# SCH_RemdesKVM_2025-04-20.net
KiCad netlist of a schematic drawn in EasyEDA
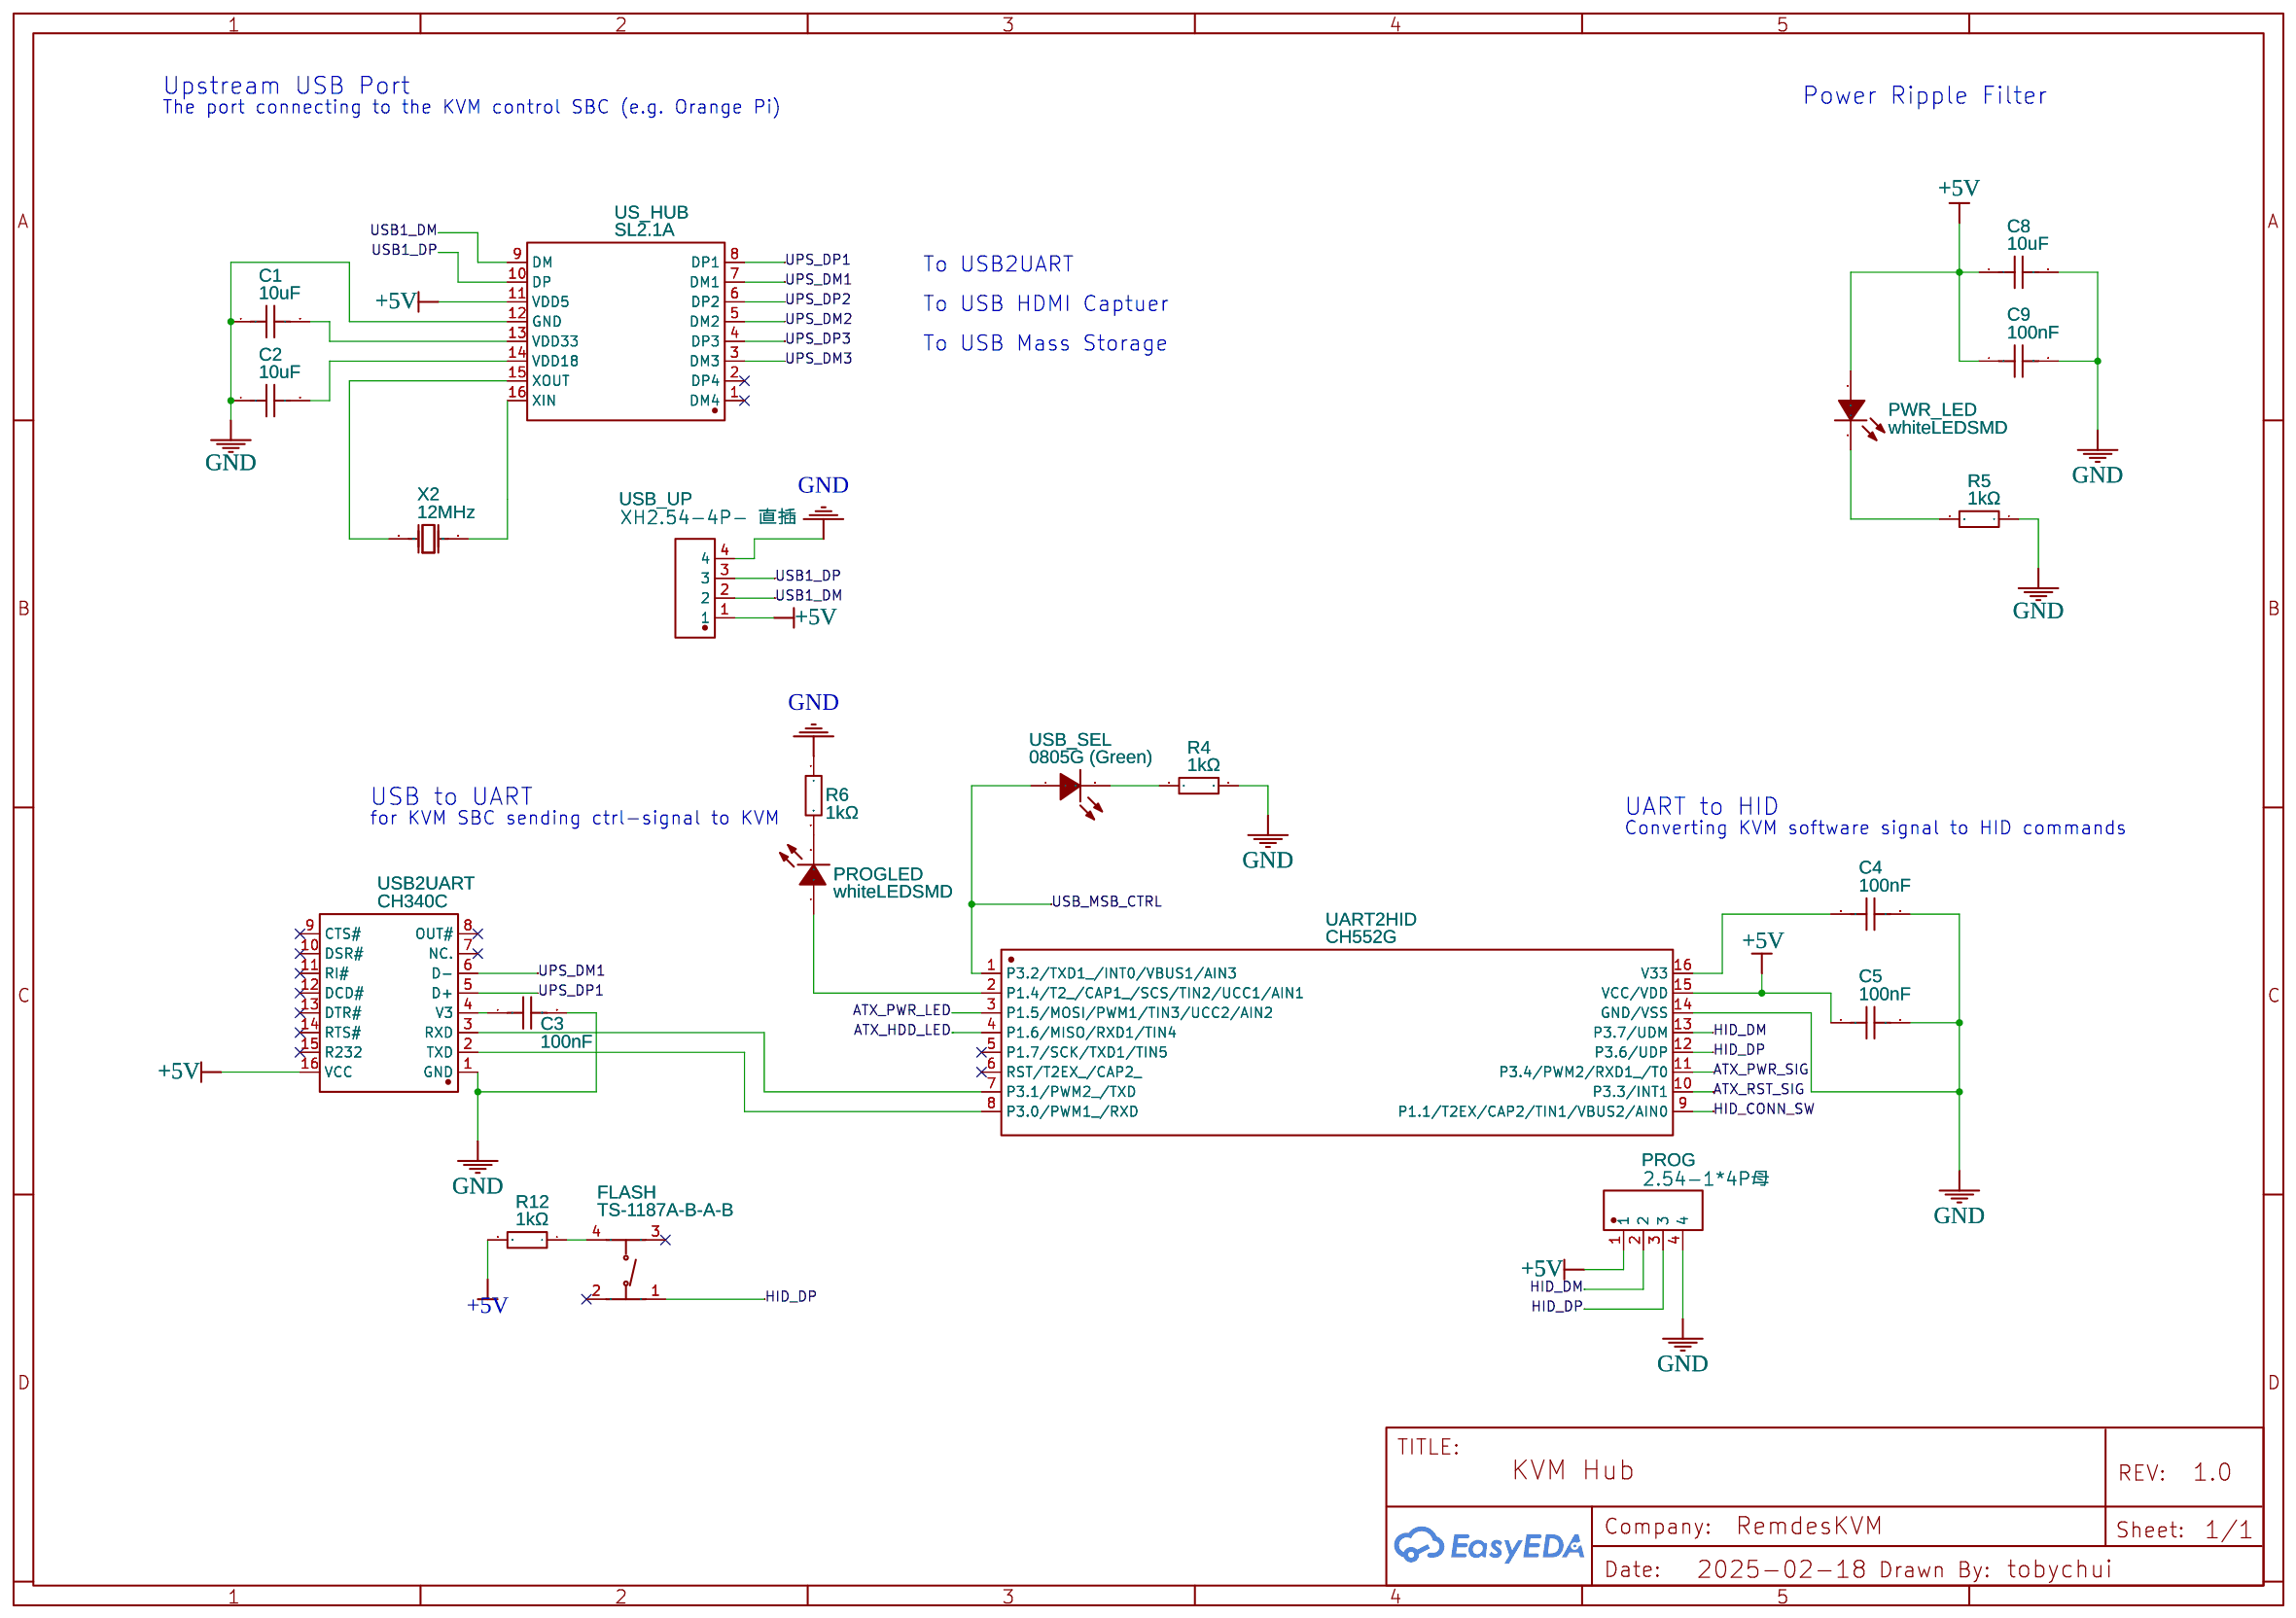
[diagram p0: KVM]
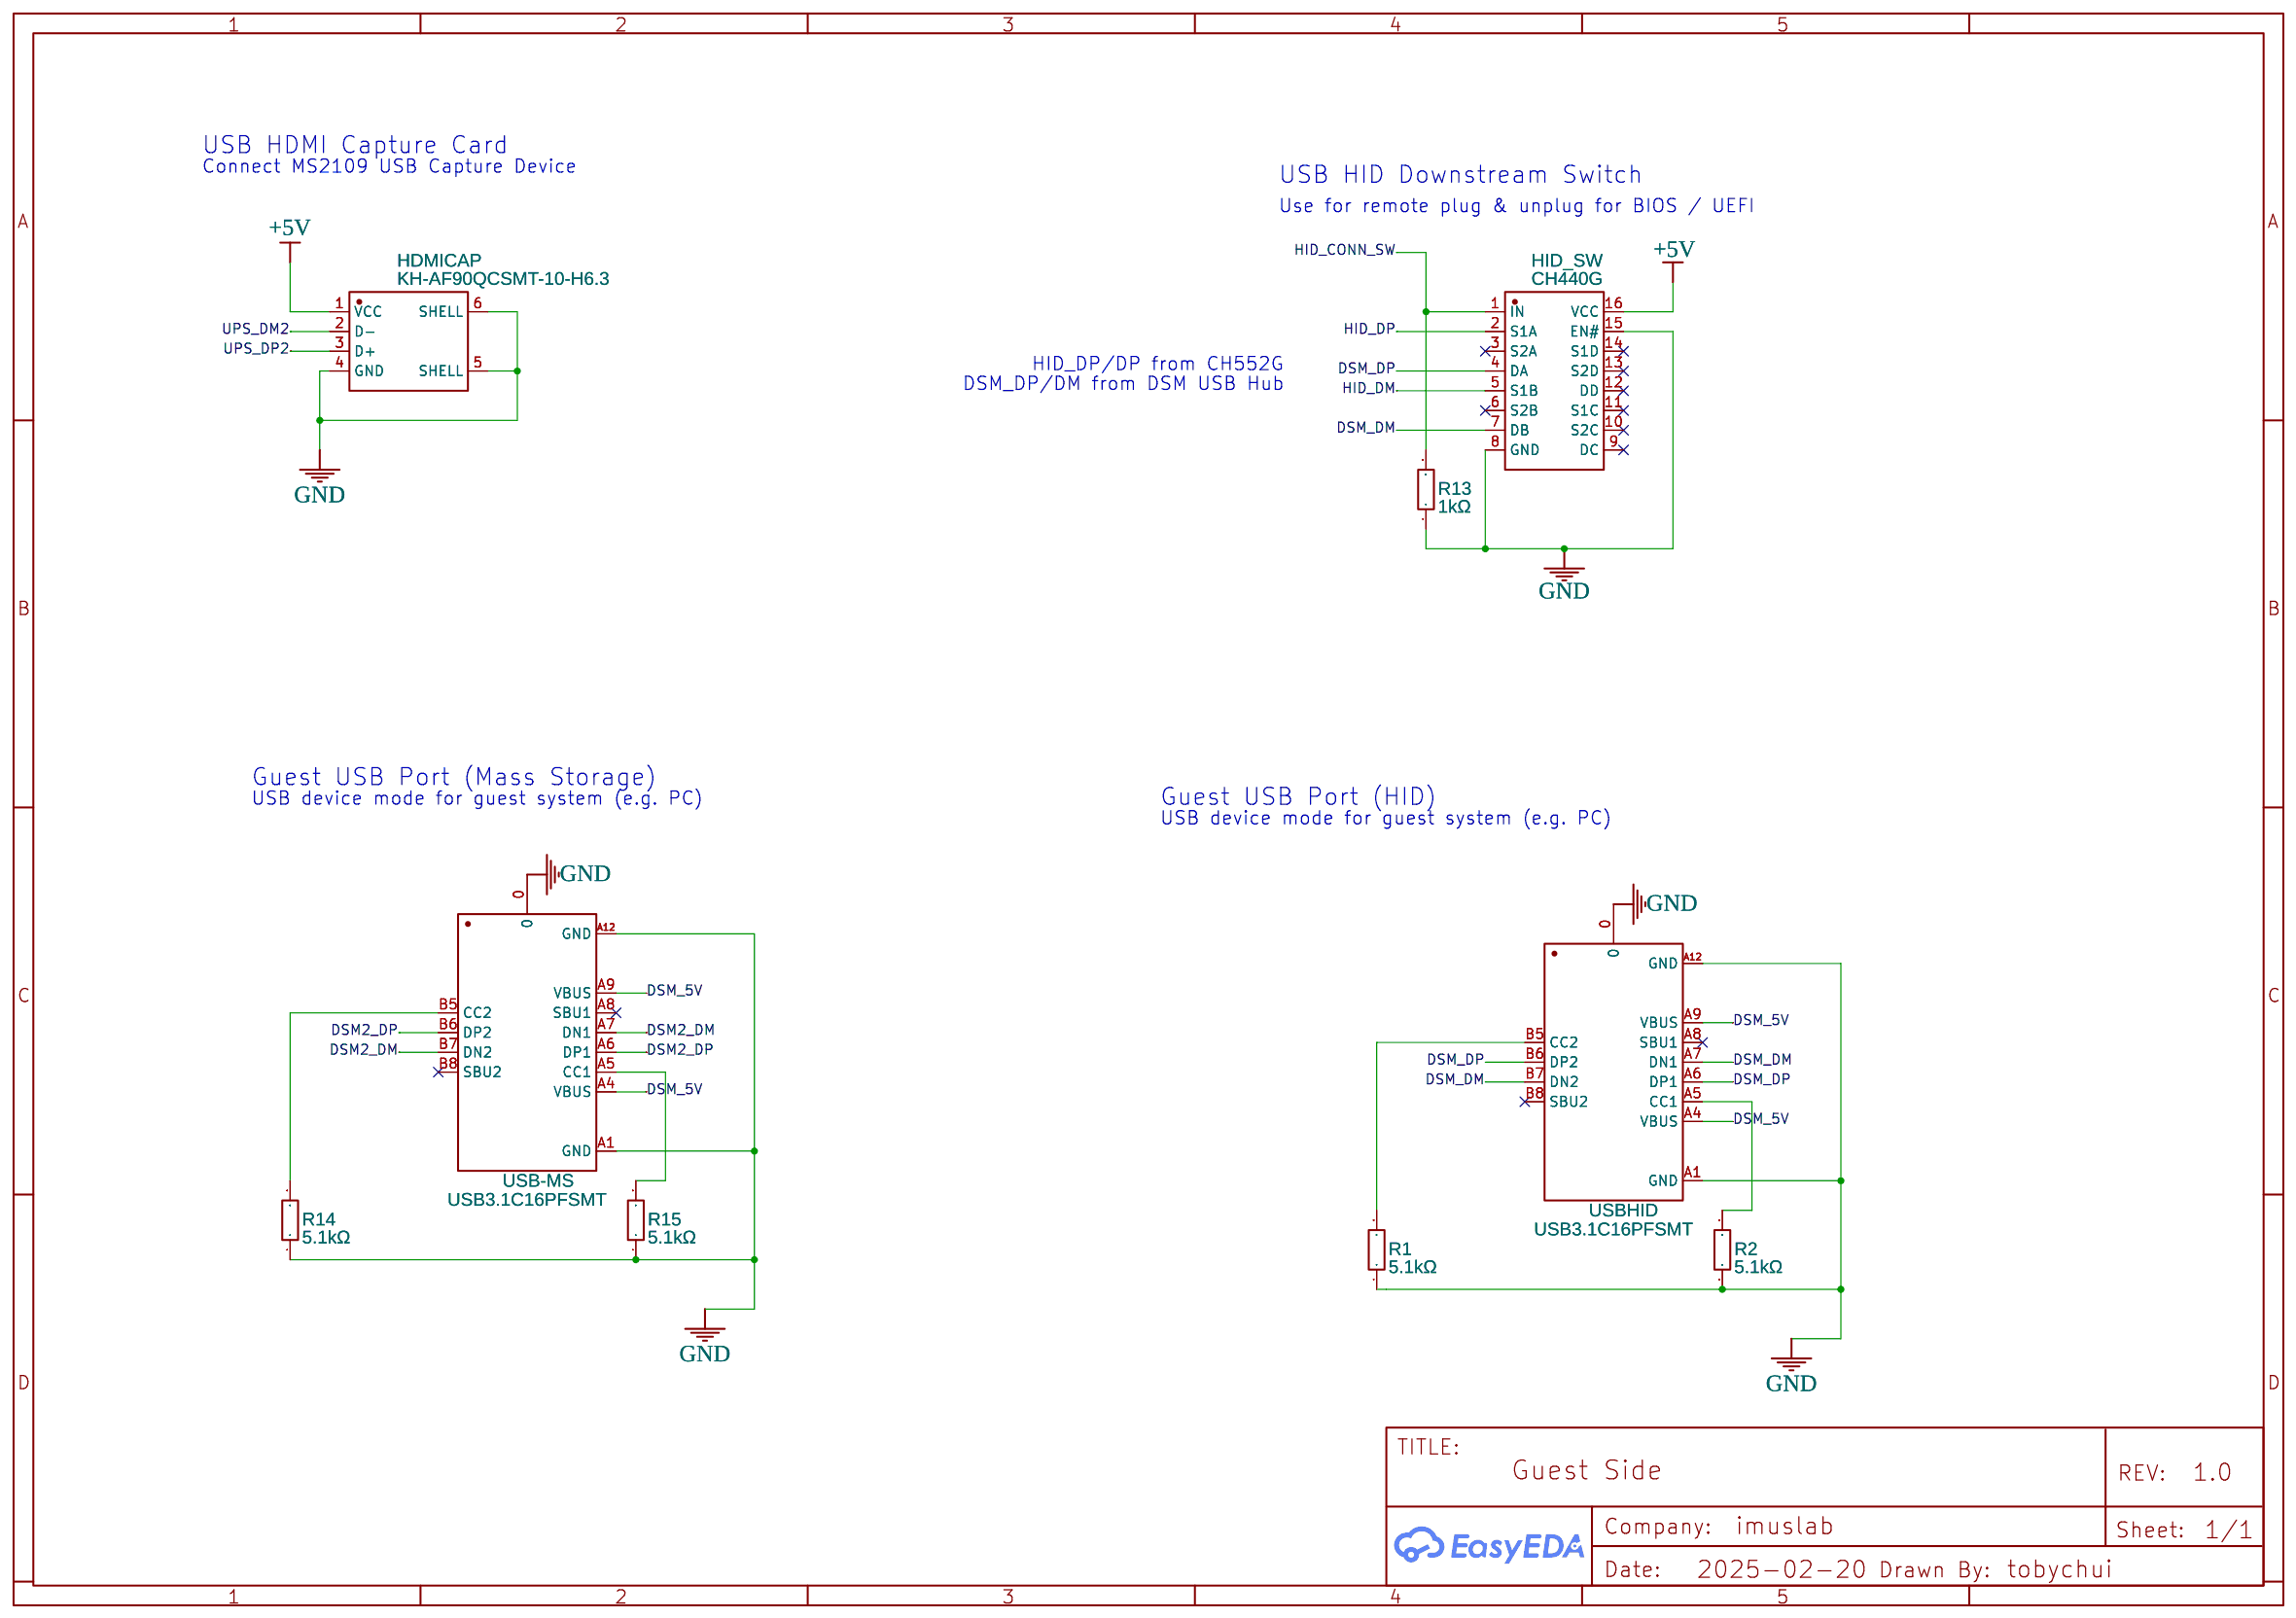
[diagram p1: Guest]
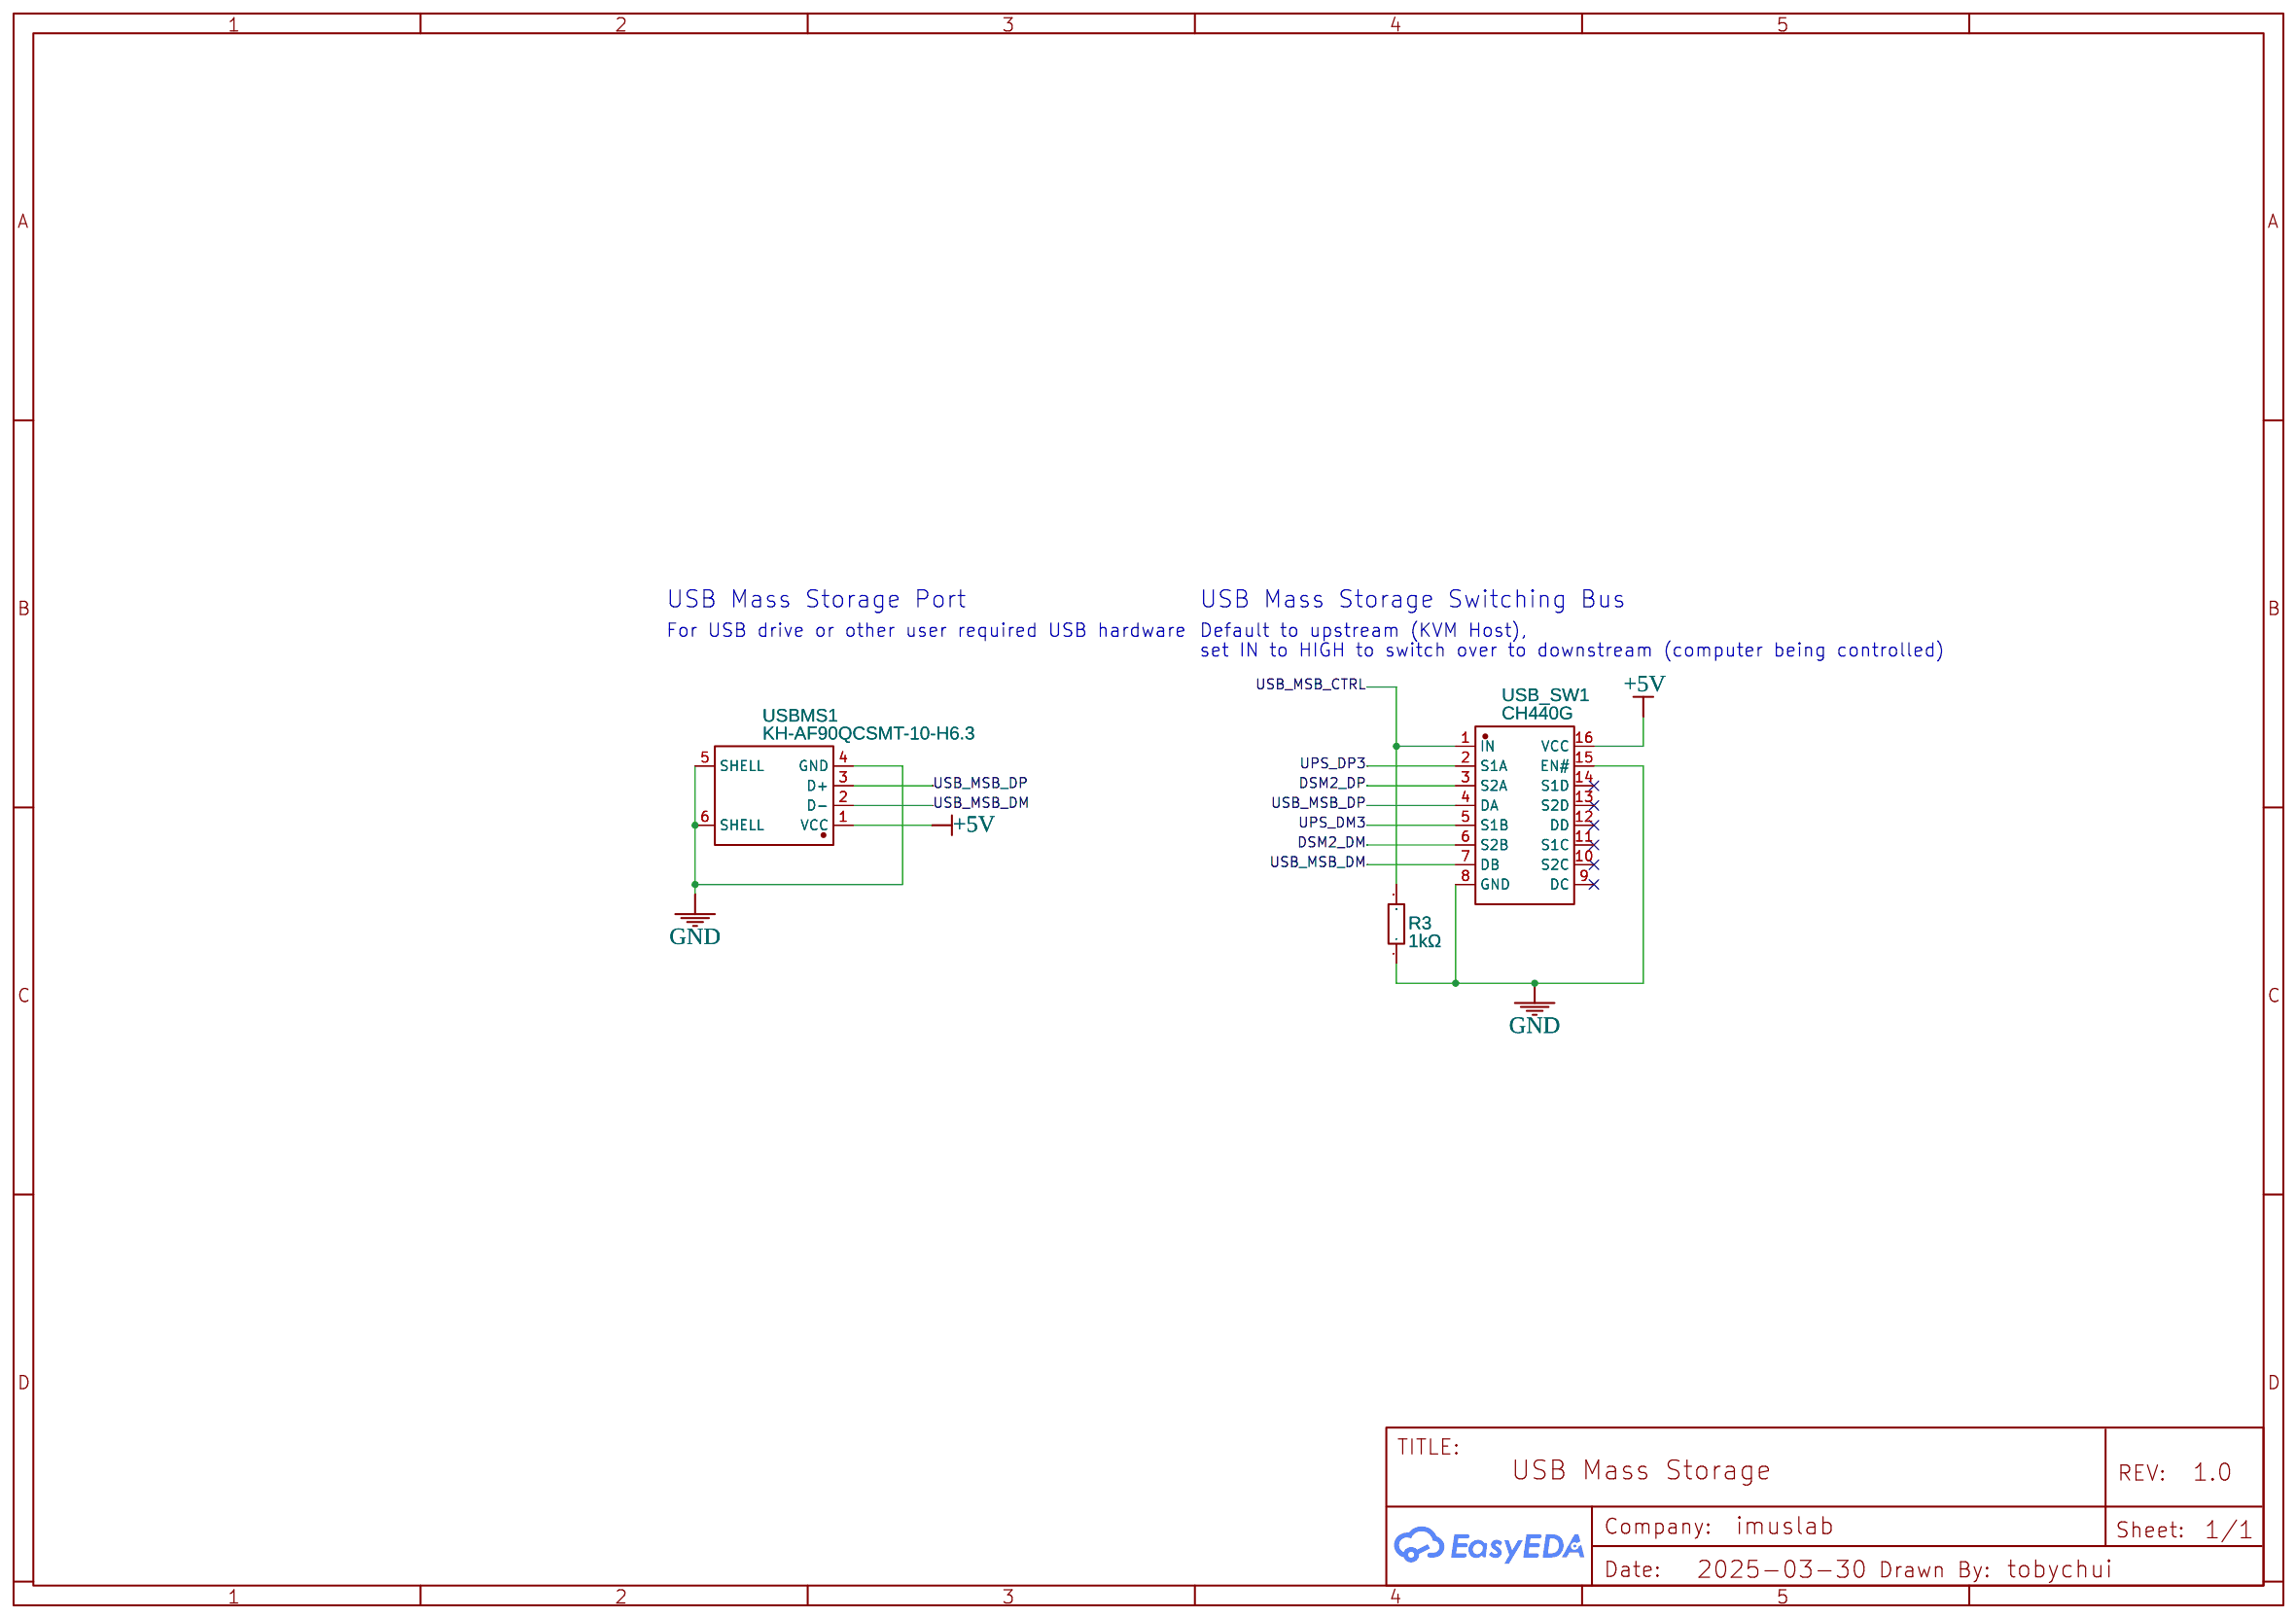
[diagram p2: USB Mass Storage]
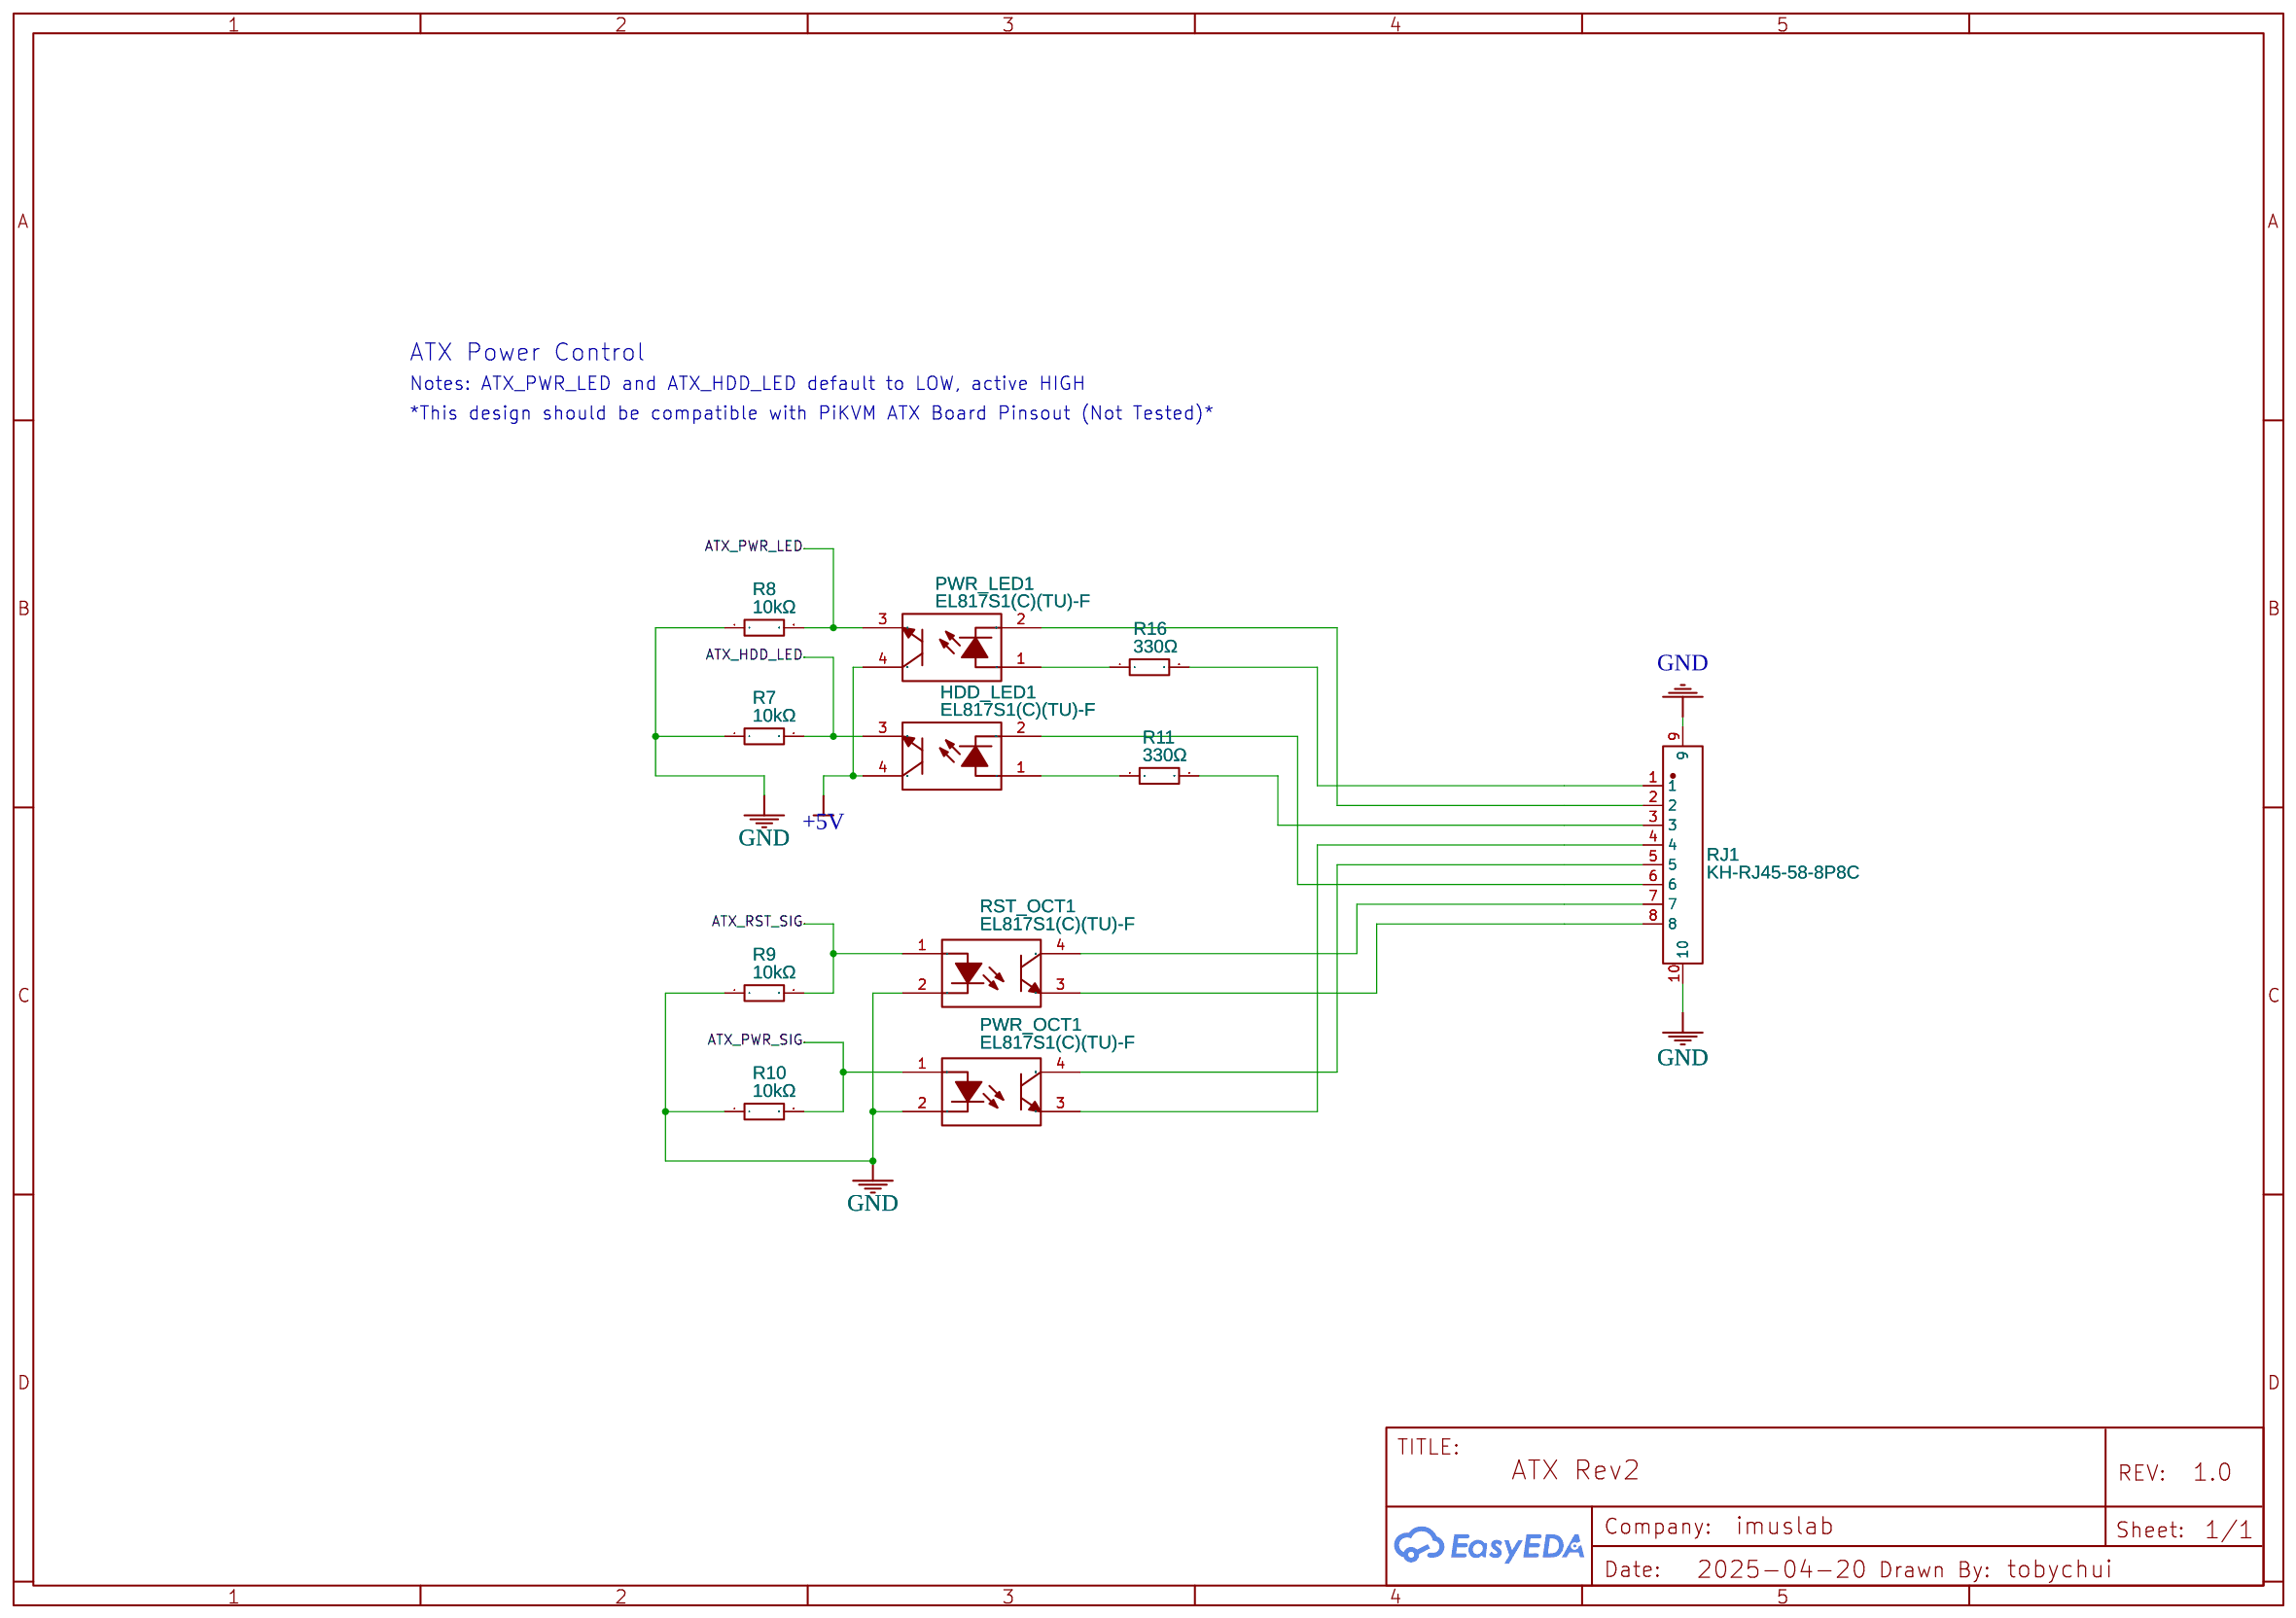
[diagram p3: ATX]

(export (version "E")
  (design (tool "Eeschema 10.0.6"))
  (components
    (comp (ref "C1")
      (value "10uF")
      (fields
        (field (name "Manufacturer Part") "CL21A106KAYNNNE")
        (field (name "Manufacturer") "SAMSUNG(三星)")
      )
      (libsource (lib "") (part "CL21A106KAYNNNE"))
    )
    (comp (ref "C2")
      (value "10uF")
      (fields
        (field (name "Manufacturer Part") "CL21A106KAYNNNE")
        (field (name "Manufacturer") "SAMSUNG(三星)")
      )
      (libsource (lib "") (part "CL21A106KAYNNNE"))
    )
    (comp (ref "C3")
      (value "100nF")
      (fields
        (field (name "Manufacturer Part") "CC0805KRX7R9BB104")
        (field (name "Manufacturer") "YAGEO(国巨)")
      )
      (libsource (lib "") (part "CC0805KRX7R9BB104"))
    )
    (comp (ref "C4")
      (value "100nF")
      (fields
        (field (name "Manufacturer Part") "CC0805KRX7R9BB104")
        (field (name "Manufacturer") "YAGEO(国巨)")
      )
      (libsource (lib "") (part "CC0805KRX7R9BB104"))
    )
    (comp (ref "C5")
      (value "100nF")
      (fields
        (field (name "Manufacturer Part") "CC0805KRX7R9BB104")
        (field (name "Manufacturer") "YAGEO(国巨)")
      )
      (libsource (lib "") (part "CC0805KRX7R9BB104"))
    )
    (comp (ref "C8")
      (value "10uF")
      (fields
        (field (name "Manufacturer Part") "CL21A106KAYNNNE")
        (field (name "Manufacturer") "SAMSUNG(三星)")
      )
      (libsource (lib "") (part "CL21A106KAYNNNE"))
    )
    (comp (ref "C9")
      (value "100nF")
      (fields
        (field (name "Manufacturer Part") "CC0805KRX7R9BB104")
        (field (name "Manufacturer") "YAGEO(国巨)")
      )
      (libsource (lib "") (part "CC0805KRX7R9BB104"))
    )
    (comp (ref "FLASH")
      (value "TS-1187A-B-A-B")
      (fields (field (name "Manufacturer") "XKB Connectivity(中国星坤)"))
      (libsource (lib "") (part "TS-1187A-B-A-B"))
    )
    (comp (ref "PROG")
      (value "2.54-1*4P母")
      (fields (field (name "Manufacturer") "BOOMELE(博穆精密)"))
      (libsource (lib "") (part "2.54-1*4P母"))
    )
    (comp (ref "PROGLED")
      (value "whiteLEDSMD")
      (fields (field (name "Manufacturer Part") "KT-0805W") (field (name "Manufacturer") "KENTO"))
      (libsource (lib "") (part "whiteLEDSMD_1"))
    )
    (comp (ref "PWR_LED")
      (value "whiteLEDSMD")
      (fields (field (name "Manufacturer Part") "KT-0805W") (field (name "Manufacturer") "KENTO"))
      (libsource (lib "") (part "whiteLEDSMD"))
    )
    (comp (ref "R4")
      (value "1kΩ")
      (fields
        (field (name "Manufacturer Part") "0805W8F1001T5E")
        (field (name "Manufacturer") "UNI-ROYAL(厚声)")
      )
      (libsource (lib "") (part "0805W8F1001T5E"))
    )
    (comp (ref "R5")
      (value "1kΩ")
      (fields
        (field (name "Manufacturer Part") "0805W8F1001T5E")
        (field (name "Manufacturer") "UNI-ROYAL(厚声)")
      )
      (libsource (lib "") (part "0805W8F1001T5E"))
    )
    (comp (ref "R6")
      (value "1kΩ")
      (fields
        (field (name "Manufacturer Part") "0805W8F1001T5E")
        (field (name "Manufacturer") "UNI-ROYAL(厚声)")
      )
      (libsource (lib "") (part "0805W8F1001T5E_1"))
    )
    (comp (ref "R12")
      (value "1kΩ")
      (fields
        (field (name "Manufacturer Part") "0805W8F1001T5E")
        (field (name "Manufacturer") "UNI-ROYAL(厚声)")
      )
      (libsource (lib "") (part "0805W8F1001T5E"))
    )
    (comp (ref "UART2HID")
      (value "CH552G")
      (fields (field (name "Manufacturer") "WCH(南京沁恒)"))
      (libsource (lib "") (part "CH552G"))
    )
    (comp (ref "USB2UART")
      (value "CH340C")
      (fields (field (name "Manufacturer") "WCH(南京沁恒)"))
      (libsource (lib "") (part "CH340C"))
    )
    (comp (ref "USB_SEL")
      (value "0805G (Green)")
      (fields (field (name "Manufacturer Part") "KT-0805G") (field (name "Manufacturer") "KENTO"))
      (libsource (lib "") (part "0805G (Green)"))
    )
    (comp (ref "USB_UP") (value "XH2.54-4P- 直插") (libsource (lib "") (part "XH2.54-4P- 直插")))
    (comp (ref "US_HUB")
      (value "SL2.1A")
      (fields (field (name "Manufacturer") "CoreChips(和芯润德)"))
      (libsource (lib "") (part "SL2.1A"))
    )
    (comp (ref "X2")
      (value "12MHz")
      (fields (field (name "Manufacturer Part") "X503212MSD2GI") (field (name "Manufacturer") "YXC(扬兴晶振)"))
      (libsource (lib "") (part "X503212MSD2GI"))
    )
    (comp (ref "HDMICAP")
      (value "KH-AF90QCSMT-10-H6.3")
      (fields (field (name "Manufacturer") "kinghelm(金航标)"))
      (libsource (lib "") (part "KH-AF90QCSMT-10-H6.3"))
    )
    (comp (ref "HID_SW")
      (value "CH440G")
      (fields (field (name "Manufacturer") "WCH(南京沁恒)"))
      (libsource (lib "") (part "CH440G"))
    )
    (comp (ref "R1")
      (value "5.1kΩ")
      (fields
        (field (name "Manufacturer Part") "0805W8F5101T5E")
        (field (name "Manufacturer") "UNI-ROYAL(厚声)")
      )
      (libsource (lib "") (part "0805W8F5101T5E"))
    )
    (comp (ref "R2")
      (value "5.1kΩ")
      (fields
        (field (name "Manufacturer Part") "0805W8F5101T5E")
        (field (name "Manufacturer") "UNI-ROYAL(厚声)")
      )
      (libsource (lib "") (part "0805W8F5101T5E"))
    )
    (comp (ref "R13")
      (value "1kΩ")
      (fields
        (field (name "Manufacturer Part") "0805W8F1001T5E")
        (field (name "Manufacturer") "UNI-ROYAL(厚声)")
      )
      (libsource (lib "") (part "0805W8F1001T5E"))
    )
    (comp (ref "R14")
      (value "5.1kΩ")
      (fields
        (field (name "Manufacturer Part") "0805W8F5101T5E")
        (field (name "Manufacturer") "UNI-ROYAL(厚声)")
      )
      (libsource (lib "") (part "0805W8F5101T5E"))
    )
    (comp (ref "R15")
      (value "5.1kΩ")
      (fields
        (field (name "Manufacturer Part") "0805W8F5101T5E")
        (field (name "Manufacturer") "UNI-ROYAL(厚声)")
      )
      (libsource (lib "") (part "0805W8F5101T5E"))
    )
    (comp (ref "USB-MS")
      (value "USB3.1C16PFSMT")
      (fields (field (name "Manufacturer Part") "918-418K2023S40001") (field (name "Manufacturer") "精拓金"))
      (libsource (lib "") (part "USB3.1C16PFSMT"))
    )
    (comp (ref "USBHID")
      (value "USB3.1C16PFSMT")
      (fields (field (name "Manufacturer Part") "918-418K2023S40001") (field (name "Manufacturer") "精拓金"))
      (libsource (lib "") (part "USB3.1C16PFSMT_1"))
    )
    (comp (ref "R3")
      (value "1kΩ")
      (fields
        (field (name "Manufacturer Part") "0805W8F1001T5E")
        (field (name "Manufacturer") "UNI-ROYAL(厚声)")
      )
      (libsource (lib "") (part "0805W8F1001T5E"))
    )
    (comp (ref "USBMS1")
      (value "KH-AF90QCSMT-10-H6.3")
      (fields (field (name "Manufacturer") "kinghelm(金航标)"))
      (libsource (lib "") (part "KH-AF90QCSMT-10-H6.3"))
    )
    (comp (ref "USB_SW1")
      (value "CH440G")
      (fields (field (name "Manufacturer") "WCH(南京沁恒)"))
      (libsource (lib "") (part "CH440G"))
    )
    (comp (ref "HDD_LED1")
      (value "EL817S1(C)(TU)-F")
      (fields (field (name "Manufacturer") "EVERLIGHT(亿光)"))
      (libsource (lib "") (part "EL817S1(C)(TU)-F_2"))
    )
    (comp (ref "PWR_LED1")
      (value "EL817S1(C)(TU)-F")
      (fields (field (name "Manufacturer") "EVERLIGHT(亿光)"))
      (libsource (lib "") (part "EL817S1(C)(TU)-F_3"))
    )
    (comp (ref "PWR_OCT1")
      (value "EL817S1(C)(TU)-F")
      (fields (field (name "Manufacturer") "EVERLIGHT(亿光)"))
      (libsource (lib "") (part "EL817S1(C)(TU)-F"))
    )
    (comp (ref "R7")
      (value "10kΩ")
      (fields
        (field (name "Manufacturer Part") "0805W8F1002T5E")
        (field (name "Manufacturer") "UNI-ROYAL(厚声)")
      )
      (libsource (lib "") (part "0805W8F1002T5E"))
    )
    (comp (ref "R8")
      (value "10kΩ")
      (fields
        (field (name "Manufacturer Part") "0805W8F1002T5E")
        (field (name "Manufacturer") "UNI-ROYAL(厚声)")
      )
      (libsource (lib "") (part "0805W8F1002T5E"))
    )
    (comp (ref "R9")
      (value "10kΩ")
      (fields
        (field (name "Manufacturer Part") "0805W8F1002T5E")
        (field (name "Manufacturer") "UNI-ROYAL(厚声)")
      )
      (libsource (lib "") (part "0805W8F1002T5E"))
    )
    (comp (ref "R10")
      (value "10kΩ")
      (fields
        (field (name "Manufacturer Part") "0805W8F1002T5E")
        (field (name "Manufacturer") "UNI-ROYAL(厚声)")
      )
      (libsource (lib "") (part "0805W8F1002T5E"))
    )
    (comp (ref "R11")
      (value "330Ω")
      (fields
        (field (name "Manufacturer Part") "0805W8F3300T5E")
        (field (name "Manufacturer") "UNI-ROYAL(厚声)")
      )
      (libsource (lib "") (part "0805W8F3300T5E"))
    )
    (comp (ref "R16")
      (value "330Ω")
      (fields
        (field (name "Manufacturer Part") "0805W8F3300T5E")
        (field (name "Manufacturer") "UNI-ROYAL(厚声)")
      )
      (libsource (lib "") (part "0805W8F3300T5E"))
    )
    (comp (ref "RJ1")
      (value "KH-RJ45-58-8P8C")
      (fields (field (name "Manufacturer") "kinghelm(金航标)"))
      (libsource (lib "") (part "KH-RJ45-58-8P8C"))
    )
    (comp (ref "RST_OCT1")
      (value "EL817S1(C)(TU)-F")
      (fields (field (name "Manufacturer") "EVERLIGHT(亿光)"))
      (libsource (lib "") (part "EL817S1(C)(TU)-F_1"))
    )
  )
  (nets
    (net (code "1") (name "+5V") (class "Default")
      (node (ref "C5") (pin "1") (pinfunction "1_1") (pintype "unspecified"))
      (node (ref "C8") (pin "1") (pinfunction "1_1") (pintype "unspecified"))
      (node (ref "C9") (pin "1") (pinfunction "1_1") (pintype "unspecified"))
      (node (ref "HDD_LED1") (pin "4") (pinfunction "COL_4") (pintype "unspecified"))
      (node (ref "HDMICAP") (pin "1") (pinfunction "VCC_1") (pintype "unspecified"))
      (node (ref "HID_SW") (pin "16") (pinfunction "VCC_16") (pintype "unspecified"))
      (node (ref "PROG") (pin "1") (pinfunction "1_1") (pintype "unspecified"))
      (node (ref "PWR_LED") (pin "1") (pinfunction "A_1") (pintype "unspecified"))
      (node (ref "PWR_LED1") (pin "4") (pinfunction "COL_4") (pintype "unspecified"))
      (node (ref "R12") (pin "2") (pinfunction "2_2") (pintype "input"))
      (node (ref "UART2HID") (pin "15") (pinfunction "VCC/VDD_15") (pintype "unspecified"))
      (node (ref "USB2UART") (pin "16") (pinfunction "VCC_16") (pintype "unspecified"))
      (node (ref "USBMS1") (pin "1") (pinfunction "VCC_1") (pintype "unspecified"))
      (node (ref "USB_SW1") (pin "16") (pinfunction "VCC_16") (pintype "unspecified"))
      (node (ref "USB_UP") (pin "1") (pinfunction "1_1") (pintype "unspecified"))
      (node (ref "US_HUB") (pin "11") (pinfunction "VDD5_11") (pintype "unspecified"))
    )
    (net (code "2") (name "ATX_HDD_LED") (class "Default")
      (node (ref "HDD_LED1") (pin "3") (pinfunction "EM_3") (pintype "unspecified"))
      (node (ref "R7") (pin "2") (pinfunction "2_2") (pintype "input"))
      (node (ref "UART2HID") (pin "4") (pinfunction "P1.6/MISO/RXD1/TIN4_4") (pintype "unspecified"))
    )
    (net (code "3") (name "ATX_PWR_LED") (class "Default")
      (node (ref "PWR_LED1") (pin "3") (pinfunction "EM_3") (pintype "unspecified"))
      (node (ref "R8") (pin "2") (pinfunction "2_2") (pintype "input"))
      (node (ref "UART2HID") (pin "3") (pinfunction "P1.5/MOSI/PWM1/TIN3/UCC2/AIN2_3") (pintype "unspecified"))
    )
    (net (code "4") (name "ATX_PWR_SIG") (class "Default")
      (node (ref "PWR_OCT1") (pin "1") (pinfunction "AN_1") (pintype "unspecified"))
      (node (ref "R10") (pin "2") (pinfunction "2_2") (pintype "input"))
      (node (ref "UART2HID") (pin "11") (pinfunction "P3.4/PWM2/RXD1_/T0_11") (pintype "unspecified"))
    )
    (net (code "5") (name "ATX_RST_SIG") (class "Default")
      (node (ref "R9") (pin "2") (pinfunction "2_2") (pintype "input"))
      (node (ref "RST_OCT1") (pin "1") (pinfunction "AN_1") (pintype "unspecified"))
      (node (ref "UART2HID") (pin "10") (pinfunction "P3.3/INT1_10") (pintype "unspecified"))
    )
    (net (code "6") (name "DSM2_DM") (class "Default")
      (node (ref "USB-MS") (pin "A7") (pinfunction "DN1_A7") (pintype "unspecified"))
      (node (ref "USB-MS") (pin "B7") (pinfunction "DN2_B7") (pintype "unspecified"))
      (node (ref "USB_SW1") (pin "6") (pinfunction "S2B_6") (pintype "unspecified"))
    )
    (net (code "7") (name "DSM2_DP") (class "Default")
      (node (ref "USB-MS") (pin "A6") (pinfunction "DP1_A6") (pintype "unspecified"))
      (node (ref "USB-MS") (pin "B6") (pinfunction "DP2_B6") (pintype "unspecified"))
      (node (ref "USB_SW1") (pin "3") (pinfunction "S2A_3") (pintype "unspecified"))
    )
    (net (code "8") (name "DSM_5V") (class "Default")
      (node (ref "USB-MS") (pin "A4") (pinfunction "VBUS_A4") (pintype "unspecified"))
      (node (ref "USB-MS") (pin "A9") (pinfunction "VBUS_A9") (pintype "unspecified"))
      (node (ref "USBHID") (pin "A4") (pinfunction "VBUS_A4") (pintype "unspecified"))
      (node (ref "USBHID") (pin "A9") (pinfunction "VBUS_A9") (pintype "unspecified"))
    )
    (net (code "9") (name "DSM_DM") (class "Default")
      (node (ref "HID_SW") (pin "7") (pinfunction "DB_7") (pintype "unspecified"))
      (node (ref "USBHID") (pin "A7") (pinfunction "DN1_A7") (pintype "unspecified"))
      (node (ref "USBHID") (pin "B7") (pinfunction "DN2_B7") (pintype "unspecified"))
    )
    (net (code "10") (name "DSM_DP") (class "Default")
      (node (ref "HID_SW") (pin "4") (pinfunction "DA_4") (pintype "unspecified"))
      (node (ref "USBHID") (pin "A6") (pinfunction "DP1_A6") (pintype "unspecified"))
      (node (ref "USBHID") (pin "B6") (pinfunction "DP2_B6") (pintype "unspecified"))
    )
    (net (code "11") (name "GND") (class "Default")
      (node (ref "C1") (pin "1") (pinfunction "1_1") (pintype "unspecified"))
      (node (ref "C2") (pin "1") (pinfunction "1_1") (pintype "unspecified"))
      (node (ref "C3") (pin "2") (pinfunction "2_2") (pintype "unspecified"))
      (node (ref "C4") (pin "2") (pinfunction "2_2") (pintype "unspecified"))
      (node (ref "C5") (pin "2") (pinfunction "2_2") (pintype "unspecified"))
      (node (ref "C8") (pin "2") (pinfunction "2_2") (pintype "unspecified"))
      (node (ref "C9") (pin "2") (pinfunction "2_2") (pintype "unspecified"))
      (node (ref "HDMICAP") (pin "4") (pinfunction "GND_4") (pintype "unspecified"))
      (node (ref "HDMICAP") (pin "5") (pinfunction "SHELL_5") (pintype "unspecified"))
      (node (ref "HDMICAP") (pin "6") (pinfunction "SHELL_6") (pintype "unspecified"))
      (node (ref "HID_SW") (pin "15") (pinfunction "EN#_15") (pintype "unspecified"))
      (node (ref "HID_SW") (pin "8") (pinfunction "GND_8") (pintype "unspecified"))
      (node (ref "PROG") (pin "4") (pinfunction "4_4") (pintype "unspecified"))
      (node (ref "PWR_OCT1") (pin "2") (pinfunction "CAT_2") (pintype "unspecified"))
      (node (ref "R1") (pin "1") (pinfunction "1_1") (pintype "input"))
      (node (ref "R10") (pin "1") (pinfunction "1_1") (pintype "input"))
      (node (ref "R13") (pin "1") (pinfunction "1_1") (pintype "input"))
      (node (ref "R14") (pin "1") (pinfunction "1_1") (pintype "input"))
      (node (ref "R15") (pin "1") (pinfunction "1_1") (pintype "input"))
      (node (ref "R2") (pin "1") (pinfunction "1_1") (pintype "input"))
      (node (ref "R3") (pin "1") (pinfunction "1_1") (pintype "input"))
      (node (ref "R4") (pin "1") (pinfunction "1_1") (pintype "input"))
      (node (ref "R5") (pin "1") (pinfunction "1_1") (pintype "input"))
      (node (ref "R6") (pin "1") (pinfunction "1_1") (pintype "input"))
      (node (ref "R7") (pin "1") (pinfunction "1_1") (pintype "input"))
      (node (ref "R8") (pin "1") (pinfunction "1_1") (pintype "input"))
      (node (ref "R9") (pin "1") (pinfunction "1_1") (pintype "input"))
      (node (ref "RJ1") (pin "10") (pinfunction "10_10") (pintype "unspecified"))
      (node (ref "RJ1") (pin "9") (pinfunction "9_9") (pintype "unspecified"))
      (node (ref "RST_OCT1") (pin "2") (pinfunction "CAT_2") (pintype "unspecified"))
      (node (ref "UART2HID") (pin "14") (pinfunction "GND/VSS_14") (pintype "unspecified"))
      (node (ref "USB-MS") (pin "0") (pinfunction "0_0") (pintype "unspecified"))
      (node (ref "USB-MS") (pin "A1") (pinfunction "GND_A1") (pintype "unspecified"))
      (node (ref "USB-MS") (pin "A12") (pinfunction "GND_A12") (pintype "unspecified"))
      (node (ref "USB2UART") (pin "1") (pinfunction "GND_1") (pintype "unspecified"))
      (node (ref "USBHID") (pin "0") (pinfunction "0_0") (pintype "unspecified"))
      (node (ref "USBHID") (pin "A1") (pinfunction "GND_A1") (pintype "unspecified"))
      (node (ref "USBHID") (pin "A12") (pinfunction "GND_A12") (pintype "unspecified"))
      (node (ref "USBMS1") (pin "4") (pinfunction "GND_4") (pintype "unspecified"))
      (node (ref "USBMS1") (pin "5") (pinfunction "SHELL_5") (pintype "unspecified"))
      (node (ref "USBMS1") (pin "6") (pinfunction "SHELL_6") (pintype "unspecified"))
      (node (ref "USB_SW1") (pin "15") (pinfunction "EN#_15") (pintype "unspecified"))
      (node (ref "USB_SW1") (pin "8") (pinfunction "GND_8") (pintype "unspecified"))
      (node (ref "USB_UP") (pin "4") (pinfunction "4_4") (pintype "unspecified"))
      (node (ref "US_HUB") (pin "12") (pinfunction "GND_12") (pintype "unspecified"))
    )
    (net (code "12") (name "HID_CONN_SW") (class "Default")
      (node (ref "HID_SW") (pin "1") (pinfunction "IN_1") (pintype "unspecified"))
      (node (ref "R13") (pin "2") (pinfunction "2_2") (pintype "input"))
      (node (ref "UART2HID") (pin "9") (pinfunction "P1.1/T2EX/CAP2/TIN1/VBUS2/AIN0_9") (pintype "unspecified"))
    )
    (net (code "13") (name "HID_DM") (class "Default")
      (node (ref "HID_SW") (pin "5") (pinfunction "S1B_5") (pintype "unspecified"))
      (node (ref "PROG") (pin "2") (pinfunction "2_2") (pintype "unspecified"))
      (node (ref "UART2HID") (pin "13") (pinfunction "P3.7/UDM_13") (pintype "unspecified"))
    )
    (net (code "14") (name "HID_DP") (class "Default")
      (node (ref "FLASH") (pin "1") (pinfunction "A_1") (pintype "unspecified"))
      (node (ref "HID_SW") (pin "2") (pinfunction "S1A_2") (pintype "unspecified"))
      (node (ref "PROG") (pin "3") (pinfunction "3_3") (pintype "unspecified"))
      (node (ref "UART2HID") (pin "12") (pinfunction "P3.6/UDP_12") (pintype "unspecified"))
    )
    (net (code "15") (name "Net-(FLASH-D)") (class "Default")
      (node (ref "FLASH") (pin "4") (pinfunction "D_4") (pintype "unspecified"))
      (node (ref "R12") (pin "1") (pinfunction "1_1") (pintype "input"))
    )
    (net (code "16") (name "Net-(HDD_LED1-AN)") (class "Default")
      (node (ref "HDD_LED1") (pin "1") (pinfunction "AN_1") (pintype "unspecified"))
      (node (ref "R11") (pin "1") (pinfunction "1_1") (pintype "input"))
    )
    (net (code "17") (name "Net-(HDD_LED1-CAT)") (class "Default")
      (node (ref "HDD_LED1") (pin "2") (pinfunction "CAT_2") (pintype "unspecified"))
      (node (ref "RJ1") (pin "6") (pinfunction "6_6") (pintype "unspecified"))
    )
    (net (code "18") (name "Net-(PROGLED-A)") (class "Default")
      (node (ref "PROGLED") (pin "1") (pinfunction "A_1") (pintype "unspecified"))
      (node (ref "UART2HID") (pin "2") (pinfunction "P1.4/T2_/CAP1_/SCS/TIN2/UCC1/AIN1_2") (pintype "unspecified"))
    )
    (net (code "19") (name "Net-(PROGLED-K)") (class "Default")
      (node (ref "PROGLED") (pin "2") (pinfunction "K_2") (pintype "unspecified"))
      (node (ref "R6") (pin "2") (pinfunction "2_2") (pintype "input"))
    )
    (net (code "20") (name "Net-(PWR_LED-K)") (class "Default")
      (node (ref "PWR_LED") (pin "2") (pinfunction "K_2") (pintype "unspecified"))
      (node (ref "R5") (pin "2") (pinfunction "2_2") (pintype "input"))
    )
    (net (code "21") (name "Net-(PWR_LED1-AN)") (class "Default")
      (node (ref "PWR_LED1") (pin "1") (pinfunction "AN_1") (pintype "unspecified"))
      (node (ref "R16") (pin "1") (pinfunction "1_1") (pintype "input"))
    )
    (net (code "22") (name "Net-(PWR_LED1-CAT)") (class "Default")
      (node (ref "PWR_LED1") (pin "2") (pinfunction "CAT_2") (pintype "unspecified"))
      (node (ref "RJ1") (pin "2") (pinfunction "2_2") (pintype "unspecified"))
    )
    (net (code "23") (name "Net-(PWR_OCT1-COL)") (class "Default")
      (node (ref "PWR_OCT1") (pin "4") (pinfunction "COL_4") (pintype "unspecified"))
      (node (ref "RJ1") (pin "5") (pinfunction "5_5") (pintype "unspecified"))
    )
    (net (code "24") (name "Net-(PWR_OCT1-EM)") (class "Default")
      (node (ref "PWR_OCT1") (pin "3") (pinfunction "EM_3") (pintype "unspecified"))
      (node (ref "RJ1") (pin "4") (pinfunction "4_4") (pintype "unspecified"))
    )
    (net (code "25") (name "Net-(R11-Pad2)") (class "Default")
      (node (ref "R11") (pin "2") (pinfunction "2_2") (pintype "input"))
      (node (ref "RJ1") (pin "3") (pinfunction "3_3") (pintype "unspecified"))
    )
    (net (code "26") (name "Net-(R16-Pad2)") (class "Default")
      (node (ref "R16") (pin "2") (pinfunction "2_2") (pintype "input"))
      (node (ref "RJ1") (pin "1") (pinfunction "1_1") (pintype "unspecified"))
    )
    (net (code "27") (name "Net-(RST_OCT1-COL)") (class "Default")
      (node (ref "RJ1") (pin "7") (pinfunction "7_7") (pintype "unspecified"))
      (node (ref "RST_OCT1") (pin "4") (pinfunction "COL_4") (pintype "unspecified"))
    )
    (net (code "28") (name "Net-(RST_OCT1-EM)") (class "Default")
      (node (ref "RJ1") (pin "8") (pinfunction "8_8") (pintype "unspecified"))
      (node (ref "RST_OCT1") (pin "3") (pinfunction "EM_3") (pintype "unspecified"))
    )
    (net (code "29") (name "Net-(UART2HID-P3.0{slash}PWM1_{slash}RXD)") (class "Default")
      (node (ref "UART2HID") (pin "8") (pinfunction "P3.0/PWM1_/RXD_8") (pintype "unspecified"))
      (node (ref "USB2UART") (pin "2") (pinfunction "TXD_2") (pintype "unspecified"))
    )
    (net (code "30") (name "Net-(UART2HID-P3.1{slash}PWM2_{slash}TXD)") (class "Default")
      (node (ref "UART2HID") (pin "7") (pinfunction "P3.1/PWM2_/TXD_7") (pintype "unspecified"))
      (node (ref "USB2UART") (pin "3") (pinfunction "RXD_3") (pintype "unspecified"))
    )
    (net (code "31") (name "Net-(UART2HID-V33)") (class "Default")
      (node (ref "C4") (pin "1") (pinfunction "1_1") (pintype "unspecified"))
      (node (ref "UART2HID") (pin "16") (pinfunction "V33_16") (pintype "unspecified"))
    )
    (net (code "32") (name "Net-(USB-MS-CC1)") (class "Default")
      (node (ref "R15") (pin "2") (pinfunction "2_2") (pintype "input"))
      (node (ref "USB-MS") (pin "A5") (pinfunction "CC1_A5") (pintype "unspecified"))
    )
    (net (code "33") (name "Net-(USB-MS-CC2)") (class "Default")
      (node (ref "R14") (pin "2") (pinfunction "2_2") (pintype "input"))
      (node (ref "USB-MS") (pin "B5") (pinfunction "CC2_B5") (pintype "unspecified"))
    )
    (net (code "34") (name "Net-(USB2UART-V3)") (class "Default")
      (node (ref "C3") (pin "1") (pinfunction "1_1") (pintype "unspecified"))
      (node (ref "USB2UART") (pin "4") (pinfunction "V3_4") (pintype "unspecified"))
    )
    (net (code "35") (name "Net-(USBHID-CC1)") (class "Default")
      (node (ref "R2") (pin "2") (pinfunction "2_2") (pintype "input"))
      (node (ref "USBHID") (pin "A5") (pinfunction "CC1_A5") (pintype "unspecified"))
    )
    (net (code "36") (name "Net-(USBHID-CC2)") (class "Default")
      (node (ref "R1") (pin "2") (pinfunction "2_2") (pintype "input"))
      (node (ref "USBHID") (pin "B5") (pinfunction "CC2_B5") (pintype "unspecified"))
    )
    (net (code "37") (name "Net-(USB_SEL-K)") (class "Default")
      (node (ref "R4") (pin "2") (pinfunction "2_2") (pintype "input"))
      (node (ref "USB_SEL") (pin "2") (pinfunction "K_2") (pintype "unspecified"))
    )
    (net (code "38") (name "Net-(US_HUB-VDD18)") (class "Default")
      (node (ref "C2") (pin "2") (pinfunction "2_2") (pintype "unspecified"))
      (node (ref "US_HUB") (pin "14") (pinfunction "VDD18_14") (pintype "unspecified"))
    )
    (net (code "39") (name "Net-(US_HUB-VDD33)") (class "Default")
      (node (ref "C1") (pin "2") (pinfunction "2_2") (pintype "unspecified"))
      (node (ref "US_HUB") (pin "13") (pinfunction "VDD33_13") (pintype "unspecified"))
    )
    (net (code "40") (name "Net-(US_HUB-XIN)") (class "Default")
      (node (ref "US_HUB") (pin "16") (pinfunction "XIN_16") (pintype "unspecified"))
      (node (ref "X2") (pin "2") (pinfunction "OSC2_2") (pintype "input"))
    )
    (net (code "41") (name "Net-(US_HUB-XOUT)") (class "Default")
      (node (ref "US_HUB") (pin "15") (pinfunction "XOUT_15") (pintype "unspecified"))
      (node (ref "X2") (pin "1") (pinfunction "OSC1_1") (pintype "input"))
    )
    (net (code "42") (name "UPS_DM1") (class "Default")
      (node (ref "USB2UART") (pin "6") (pinfunction "D-_6") (pintype "unspecified"))
      (node (ref "US_HUB") (pin "7") (pinfunction "DM1_7") (pintype "unspecified"))
    )
    (net (code "43") (name "UPS_DM2") (class "Default")
      (node (ref "HDMICAP") (pin "2") (pinfunction "D-_2") (pintype "unspecified"))
      (node (ref "US_HUB") (pin "5") (pinfunction "DM2_5") (pintype "unspecified"))
    )
    (net (code "44") (name "UPS_DM3") (class "Default")
      (node (ref "USB_SW1") (pin "5") (pinfunction "S1B_5") (pintype "unspecified"))
      (node (ref "US_HUB") (pin "3") (pinfunction "DM3_3") (pintype "unspecified"))
    )
    (net (code "45") (name "UPS_DP1") (class "Default")
      (node (ref "USB2UART") (pin "5") (pinfunction "D+_5") (pintype "unspecified"))
      (node (ref "US_HUB") (pin "8") (pinfunction "DP1_8") (pintype "unspecified"))
    )
    (net (code "46") (name "UPS_DP2") (class "Default")
      (node (ref "HDMICAP") (pin "3") (pinfunction "D+_3") (pintype "unspecified"))
      (node (ref "US_HUB") (pin "6") (pinfunction "DP2_6") (pintype "unspecified"))
    )
    (net (code "47") (name "UPS_DP3") (class "Default")
      (node (ref "USB_SW1") (pin "2") (pinfunction "S1A_2") (pintype "unspecified"))
      (node (ref "US_HUB") (pin "4") (pinfunction "DP3_4") (pintype "unspecified"))
    )
    (net (code "48") (name "USB1_DM") (class "Default")
      (node (ref "USB_UP") (pin "2") (pinfunction "2_2") (pintype "unspecified"))
      (node (ref "US_HUB") (pin "9") (pinfunction "DM_9") (pintype "unspecified"))
    )
    (net (code "49") (name "USB1_DP") (class "Default")
      (node (ref "USB_UP") (pin "3") (pinfunction "3_3") (pintype "unspecified"))
      (node (ref "US_HUB") (pin "10") (pinfunction "DP_10") (pintype "unspecified"))
    )
    (net (code "50") (name "USB_MSB_CTRL") (class "Default")
      (node (ref "R3") (pin "2") (pinfunction "2_2") (pintype "input"))
      (node (ref "UART2HID") (pin "1") (pinfunction "P3.2/TXD1_/INT0/VBUS1/AIN3_1") (pintype "unspecified"))
      (node (ref "USB_SEL") (pin "1") (pinfunction "A_1") (pintype "unspecified"))
      (node (ref "USB_SW1") (pin "1") (pinfunction "IN_1") (pintype "unspecified"))
    )
    (net (code "51") (name "USB_MSB_DM") (class "Default")
      (node (ref "USBMS1") (pin "2") (pinfunction "D-_2") (pintype "unspecified"))
      (node (ref "USB_SW1") (pin "7") (pinfunction "DB_7") (pintype "unspecified"))
    )
    (net (code "52") (name "USB_MSB_DP") (class "Default")
      (node (ref "USBMS1") (pin "3") (pinfunction "D+_3") (pintype "unspecified"))
      (node (ref "USB_SW1") (pin "4") (pinfunction "DA_4") (pintype "unspecified"))
    )
    (net (code "53") (name "unconnected-(FLASH-B-Pad2)") (class "Default")
      (node (ref "FLASH") (pin "2") (pinfunction "B_2") (pintype "unspecified+no_connect"))
    )
    (net (code "54") (name "unconnected-(FLASH-C-Pad3)") (class "Default")
      (node (ref "FLASH") (pin "3") (pinfunction "C_3") (pintype "unspecified+no_connect"))
    )
    (net (code "55") (name "unconnected-(HID_SW-DC-Pad9)") (class "Default")
      (node (ref "HID_SW") (pin "9") (pinfunction "DC_9") (pintype "unspecified+no_connect"))
    )
    (net (code "56") (name "unconnected-(HID_SW-DD-Pad12)") (class "Default")
      (node (ref "HID_SW") (pin "12") (pinfunction "DD_12") (pintype "unspecified+no_connect"))
    )
    (net (code "57") (name "unconnected-(HID_SW-S1C-Pad11)") (class "Default")
      (node (ref "HID_SW") (pin "11") (pinfunction "S1C_11") (pintype "unspecified+no_connect"))
    )
    (net (code "58") (name "unconnected-(HID_SW-S1D-Pad14)") (class "Default")
      (node (ref "HID_SW") (pin "14") (pinfunction "S1D_14") (pintype "unspecified+no_connect"))
    )
    (net (code "59") (name "unconnected-(HID_SW-S2A-Pad3)") (class "Default")
      (node (ref "HID_SW") (pin "3") (pinfunction "S2A_3") (pintype "unspecified+no_connect"))
    )
    (net (code "60") (name "unconnected-(HID_SW-S2B-Pad6)") (class "Default")
      (node (ref "HID_SW") (pin "6") (pinfunction "S2B_6") (pintype "unspecified+no_connect"))
    )
    (net (code "61") (name "unconnected-(HID_SW-S2C-Pad10)") (class "Default")
      (node (ref "HID_SW") (pin "10") (pinfunction "S2C_10") (pintype "unspecified+no_connect"))
    )
    (net (code "62") (name "unconnected-(HID_SW-S2D-Pad13)") (class "Default")
      (node (ref "HID_SW") (pin "13") (pinfunction "S2D_13") (pintype "unspecified+no_connect"))
    )
    (net (code "63") (name "unconnected-(UART2HID-P1.7{slash}SCK{slash}TXD1{slash}TIN5-Pad5)") (class "Default")
      (node (ref "UART2HID") (pin "5") (pinfunction "P1.7/SCK/TXD1/TIN5_5") (pintype "unspecified+no_connect"))
    )
    (net (code "64") (name "unconnected-(UART2HID-RST{slash}T2EX_{slash}CAP2_-Pad6)") (class "Default")
      (node (ref "UART2HID") (pin "6") (pinfunction "RST/T2EX_/CAP2__6") (pintype "unspecified+no_connect"))
    )
    (net (code "65") (name "unconnected-(USB-MS-SBU1-PadA8)") (class "Default")
      (node (ref "USB-MS") (pin "A8") (pinfunction "SBU1_A8") (pintype "unspecified+no_connect"))
    )
    (net (code "66") (name "unconnected-(USB-MS-SBU2-PadB8)") (class "Default")
      (node (ref "USB-MS") (pin "B8") (pinfunction "SBU2_B8") (pintype "unspecified+no_connect"))
    )
    (net (code "67") (name "unconnected-(USB2UART-CTS#-Pad9)") (class "Default")
      (node (ref "USB2UART") (pin "9") (pinfunction "CTS#_9") (pintype "unspecified+no_connect"))
    )
    (net (code "68") (name "unconnected-(USB2UART-DCD#-Pad12)") (class "Default")
      (node (ref "USB2UART") (pin "12") (pinfunction "DCD#_12") (pintype "unspecified+no_connect"))
    )
    (net (code "69") (name "unconnected-(USB2UART-DSR#-Pad10)") (class "Default")
      (node (ref "USB2UART") (pin "10") (pinfunction "DSR#_10") (pintype "unspecified+no_connect"))
    )
    (net (code "70") (name "unconnected-(USB2UART-DTR#-Pad13)") (class "Default")
      (node (ref "USB2UART") (pin "13") (pinfunction "DTR#_13") (pintype "unspecified+no_connect"))
    )
    (net (code "71") (name "unconnected-(USB2UART-NC.-Pad7)") (class "Default")
      (node (ref "USB2UART") (pin "7") (pinfunction "NC._7") (pintype "unspecified+no_connect"))
    )
    (net (code "72") (name "unconnected-(USB2UART-OUT#-Pad8)") (class "Default")
      (node (ref "USB2UART") (pin "8") (pinfunction "OUT#_8") (pintype "unspecified+no_connect"))
    )
    (net (code "73") (name "unconnected-(USB2UART-R232-Pad15)") (class "Default")
      (node (ref "USB2UART") (pin "15") (pinfunction "R232_15") (pintype "unspecified+no_connect"))
    )
    (net (code "74") (name "unconnected-(USB2UART-RI#-Pad11)") (class "Default")
      (node (ref "USB2UART") (pin "11") (pinfunction "RI#_11") (pintype "unspecified+no_connect"))
    )
    (net (code "75") (name "unconnected-(USB2UART-RTS#-Pad14)") (class "Default")
      (node (ref "USB2UART") (pin "14") (pinfunction "RTS#_14") (pintype "unspecified+no_connect"))
    )
    (net (code "76") (name "unconnected-(USBHID-SBU1-PadA8)") (class "Default")
      (node (ref "USBHID") (pin "A8") (pinfunction "SBU1_A8") (pintype "unspecified+no_connect"))
    )
    (net (code "77") (name "unconnected-(USBHID-SBU2-PadB8)") (class "Default")
      (node (ref "USBHID") (pin "B8") (pinfunction "SBU2_B8") (pintype "unspecified+no_connect"))
    )
    (net (code "78") (name "unconnected-(USB_SW1-DC-Pad9)") (class "Default")
      (node (ref "USB_SW1") (pin "9") (pinfunction "DC_9") (pintype "unspecified+no_connect"))
    )
    (net (code "79") (name "unconnected-(USB_SW1-DD-Pad12)") (class "Default")
      (node (ref "USB_SW1") (pin "12") (pinfunction "DD_12") (pintype "unspecified+no_connect"))
    )
    (net (code "80") (name "unconnected-(USB_SW1-S1C-Pad11)") (class "Default")
      (node (ref "USB_SW1") (pin "11") (pinfunction "S1C_11") (pintype "unspecified+no_connect"))
    )
    (net (code "81") (name "unconnected-(USB_SW1-S1D-Pad14)") (class "Default")
      (node (ref "USB_SW1") (pin "14") (pinfunction "S1D_14") (pintype "unspecified+no_connect"))
    )
    (net (code "82") (name "unconnected-(USB_SW1-S2C-Pad10)") (class "Default")
      (node (ref "USB_SW1") (pin "10") (pinfunction "S2C_10") (pintype "unspecified+no_connect"))
    )
    (net (code "83") (name "unconnected-(USB_SW1-S2D-Pad13)") (class "Default")
      (node (ref "USB_SW1") (pin "13") (pinfunction "S2D_13") (pintype "unspecified+no_connect"))
    )
    (net (code "84") (name "unconnected-(US_HUB-DM4-Pad1)") (class "Default")
      (node (ref "US_HUB") (pin "1") (pinfunction "DM4_1") (pintype "unspecified+no_connect"))
    )
    (net (code "85") (name "unconnected-(US_HUB-DP4-Pad2)") (class "Default")
      (node (ref "US_HUB") (pin "2") (pinfunction "DP4_2") (pintype "unspecified+no_connect"))
    )
  )
)
